# SCH_ajax-mqtt_2022-05-22.net
KiCad netlist of a schematic drawn in EasyEDA
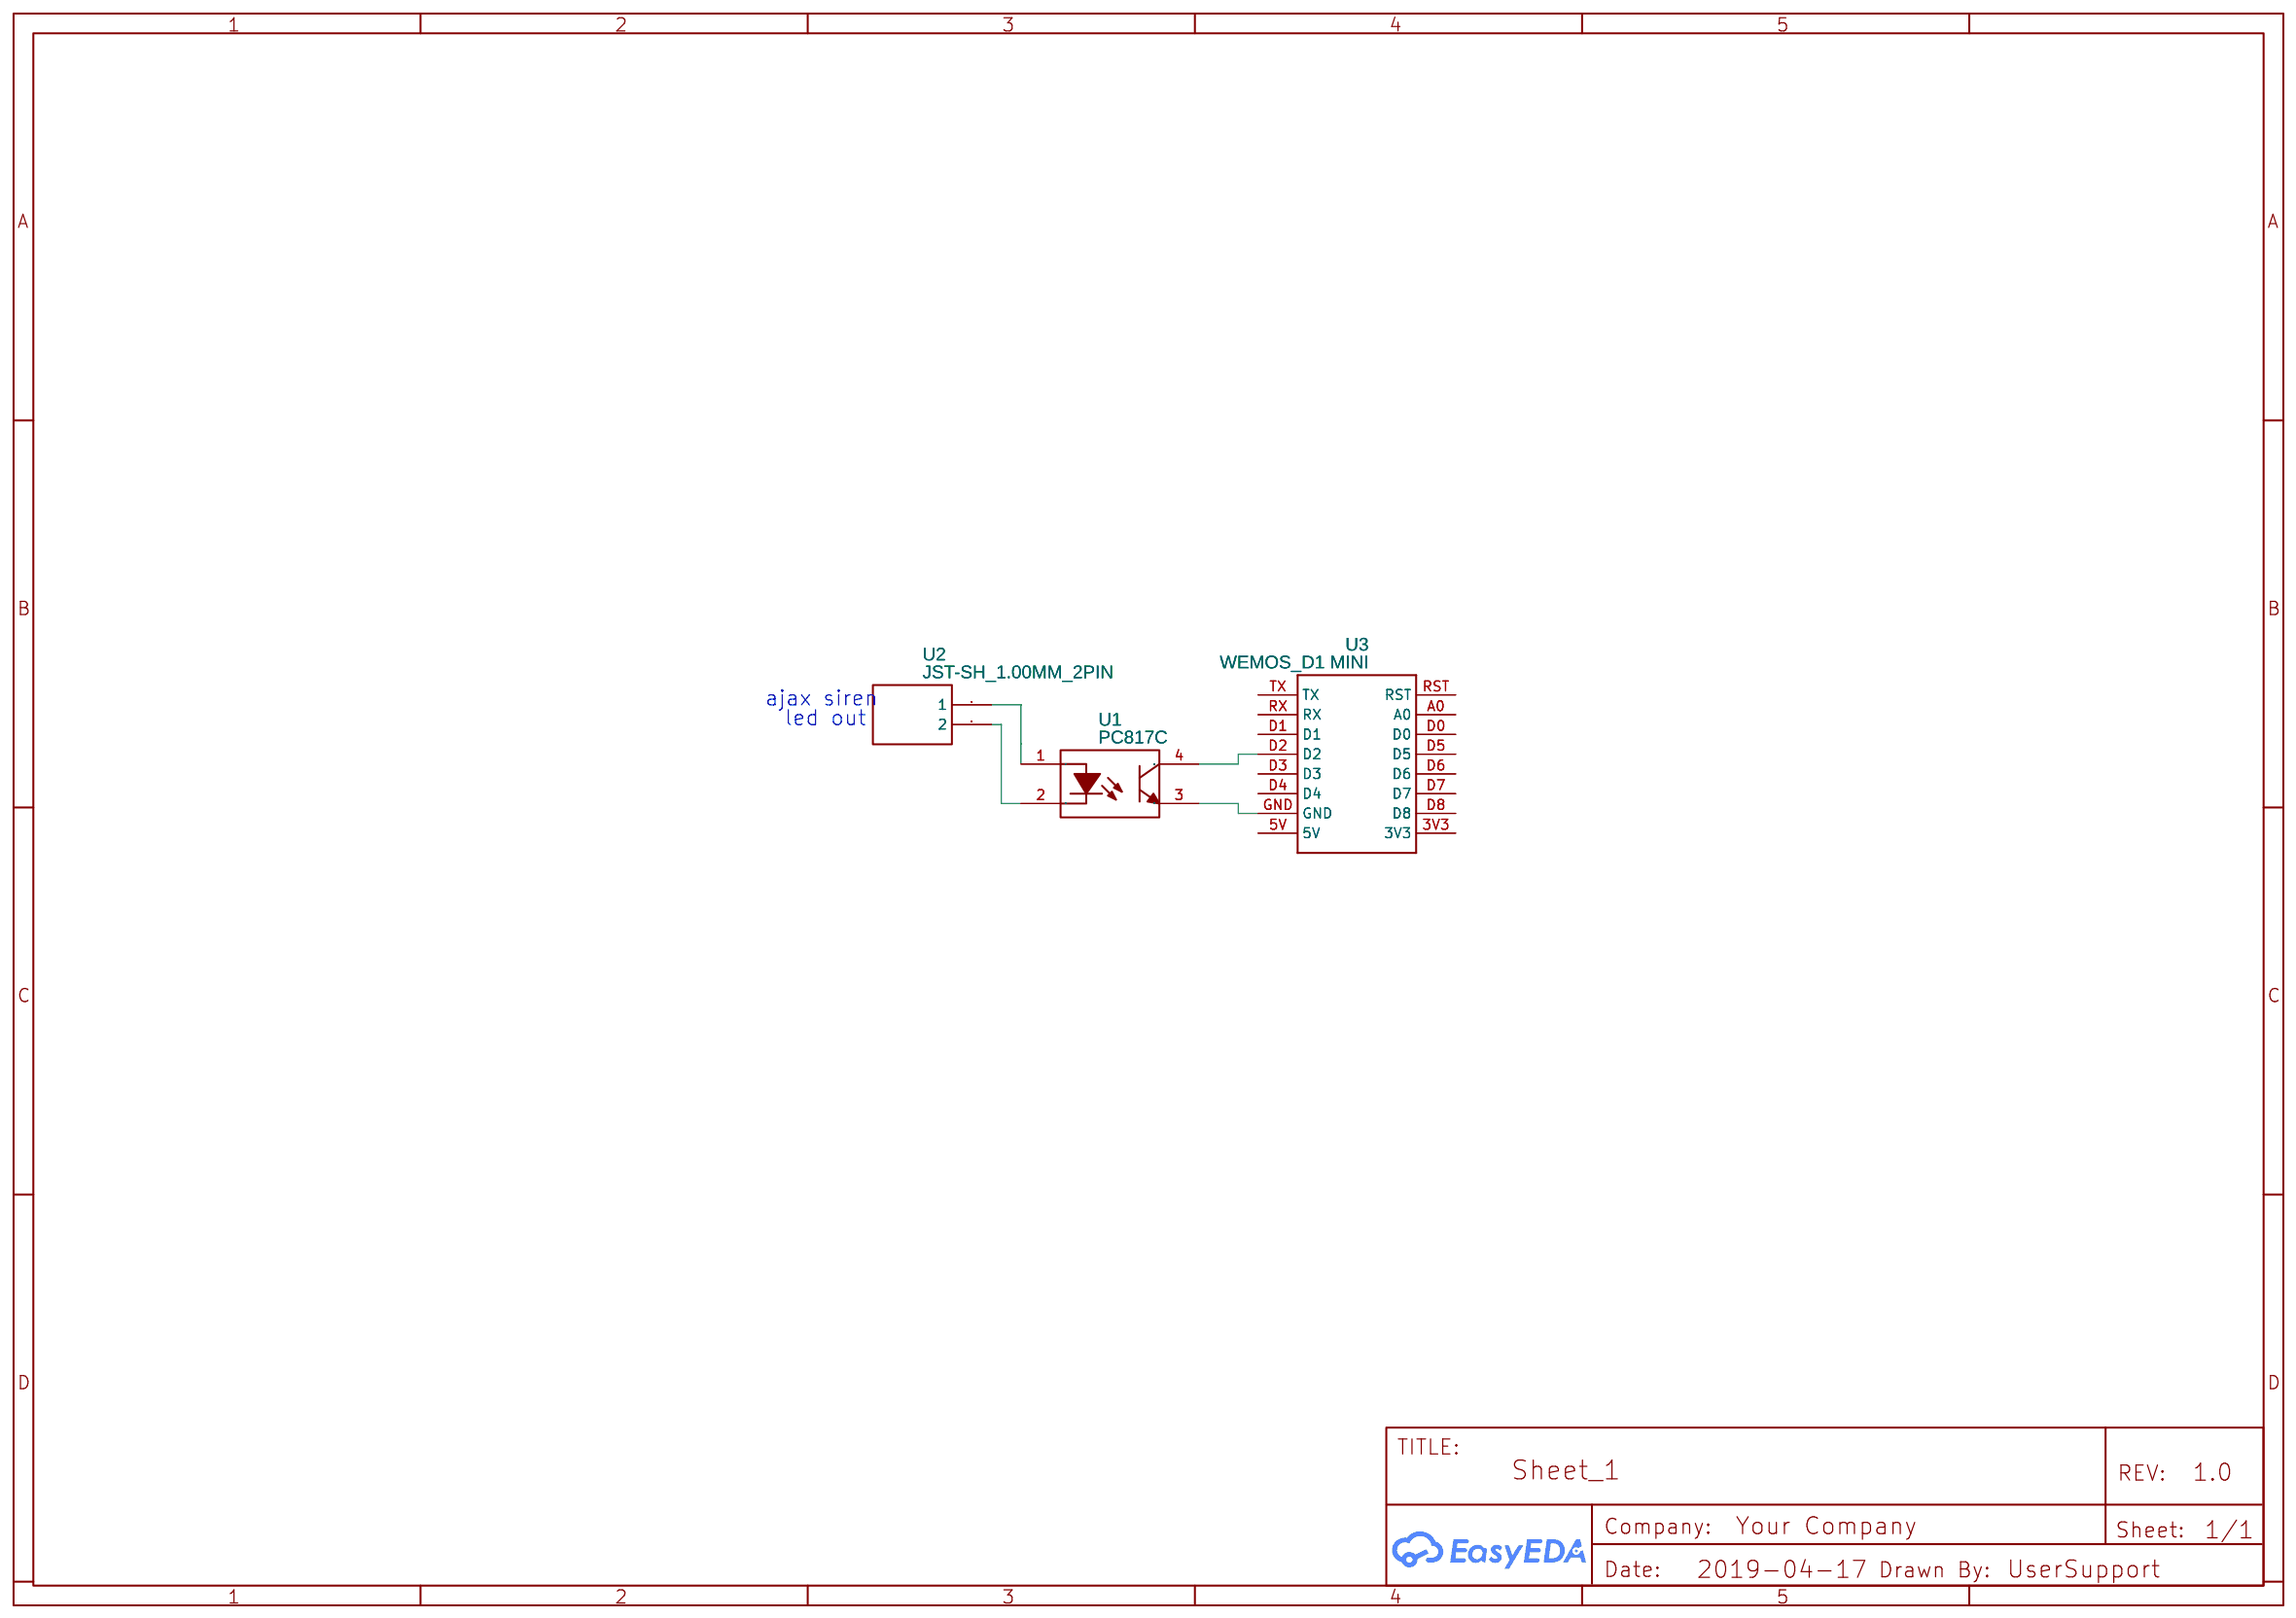
[diagram p0: schematic sheet]

(export (version "E")
  (design (tool "Eeschema 10.0.6"))
  (components
    (comp (ref "U1")
      (value "PC817C")
      (fields (field (name "BOM_Supplier Part") "C115500"))
      (libsource (lib "") (part "Unknown_550_390"))
    )
    (comp (ref "U2")
      (value "JST-SH_1.00MM_2PIN")
      (fields (field (name "BOM_Manufacturer Part") "?") (field (name "BOM_Supplier Part") "undefined"))
      (libsource (lib "") (part "Unknown_495_350"))
    )
    (comp (ref "U3")
      (value "WEMOS_D1 MINI")
      (fields (field (name "BOM_Manufacturer Part") "?"))
      (libsource (lib "") (part "Unknown_710_425"))
    )
  )
  (nets
    (net (code "1") (name "Net-(U1-AN)") (class "Default")
      (node (ref "U1") (pin "1") (pinfunction "AN_1") (pintype "unspecified"))
      (node (ref "U2") (pin "1") (pinfunction "1_1") (pintype "unspecified"))
    )
    (net (code "2") (name "Net-(U1-CAT)") (class "Default")
      (node (ref "U1") (pin "2") (pinfunction "CAT_2") (pintype "unspecified"))
      (node (ref "U2") (pin "2") (pinfunction "2_2") (pintype "unspecified"))
    )
    (net (code "3") (name "Net-(U1-COL)") (class "Default")
      (node (ref "U1") (pin "4") (pinfunction "COL_4") (pintype "unspecified"))
      (node (ref "U3") (pin "D2") (pinfunction "D2_D2") (pintype "unspecified"))
    )
    (net (code "4") (name "Net-(U1-EM)") (class "Default")
      (node (ref "U1") (pin "3") (pinfunction "EM_3") (pintype "unspecified"))
      (node (ref "U3") (pin "GND") (pinfunction "GND_GND") (pintype "unspecified"))
    )
    (net (code "5") (name "unconnected-(U3-Pad3V3)") (class "Default")
      (node (ref "U3") (pin "3V3") (pinfunction "3V3_3V3") (pintype "unspecified"))
    )
    (net (code "6") (name "unconnected-(U3-Pad5V)") (class "Default")
      (node (ref "U3") (pin "5V") (pinfunction "5V_5V") (pintype "unspecified"))
    )
    (net (code "7") (name "unconnected-(U3-PadA0)") (class "Default")
      (node (ref "U3") (pin "A0") (pinfunction "A0_A0") (pintype "unspecified"))
    )
    (net (code "8") (name "unconnected-(U3-PadD0)") (class "Default")
      (node (ref "U3") (pin "D0") (pinfunction "D0_D0") (pintype "unspecified"))
    )
    (net (code "9") (name "unconnected-(U3-PadD1)") (class "Default")
      (node (ref "U3") (pin "D1") (pinfunction "D1_D1") (pintype "unspecified"))
    )
    (net (code "10") (name "unconnected-(U3-PadD3)") (class "Default")
      (node (ref "U3") (pin "D3") (pinfunction "D3_D3") (pintype "unspecified"))
    )
    (net (code "11") (name "unconnected-(U3-PadD4)") (class "Default")
      (node (ref "U3") (pin "D4") (pinfunction "D4_D4") (pintype "unspecified"))
    )
    (net (code "12") (name "unconnected-(U3-PadD5)") (class "Default")
      (node (ref "U3") (pin "D5") (pinfunction "D5_D5") (pintype "unspecified"))
    )
    (net (code "13") (name "unconnected-(U3-PadD6)") (class "Default")
      (node (ref "U3") (pin "D6") (pinfunction "D6_D6") (pintype "unspecified"))
    )
    (net (code "14") (name "unconnected-(U3-PadD7)") (class "Default")
      (node (ref "U3") (pin "D7") (pinfunction "D7_D7") (pintype "unspecified"))
    )
    (net (code "15") (name "unconnected-(U3-PadD8)") (class "Default")
      (node (ref "U3") (pin "D8") (pinfunction "D8_D8") (pintype "unspecified"))
    )
    (net (code "16") (name "unconnected-(U3-PadRST)") (class "Default")
      (node (ref "U3") (pin "RST") (pinfunction "RST_RST") (pintype "unspecified"))
    )
    (net (code "17") (name "unconnected-(U3-PadRX)") (class "Default")
      (node (ref "U3") (pin "RX") (pinfunction "RX_RX") (pintype "unspecified"))
    )
    (net (code "18") (name "unconnected-(U3-PadTX)") (class "Default")
      (node (ref "U3") (pin "TX") (pinfunction "TX_TX") (pintype "unspecified"))
    )
  )
)
